# cpu_board.net
KiCad netlist of a schematic drawn in Altium Designer
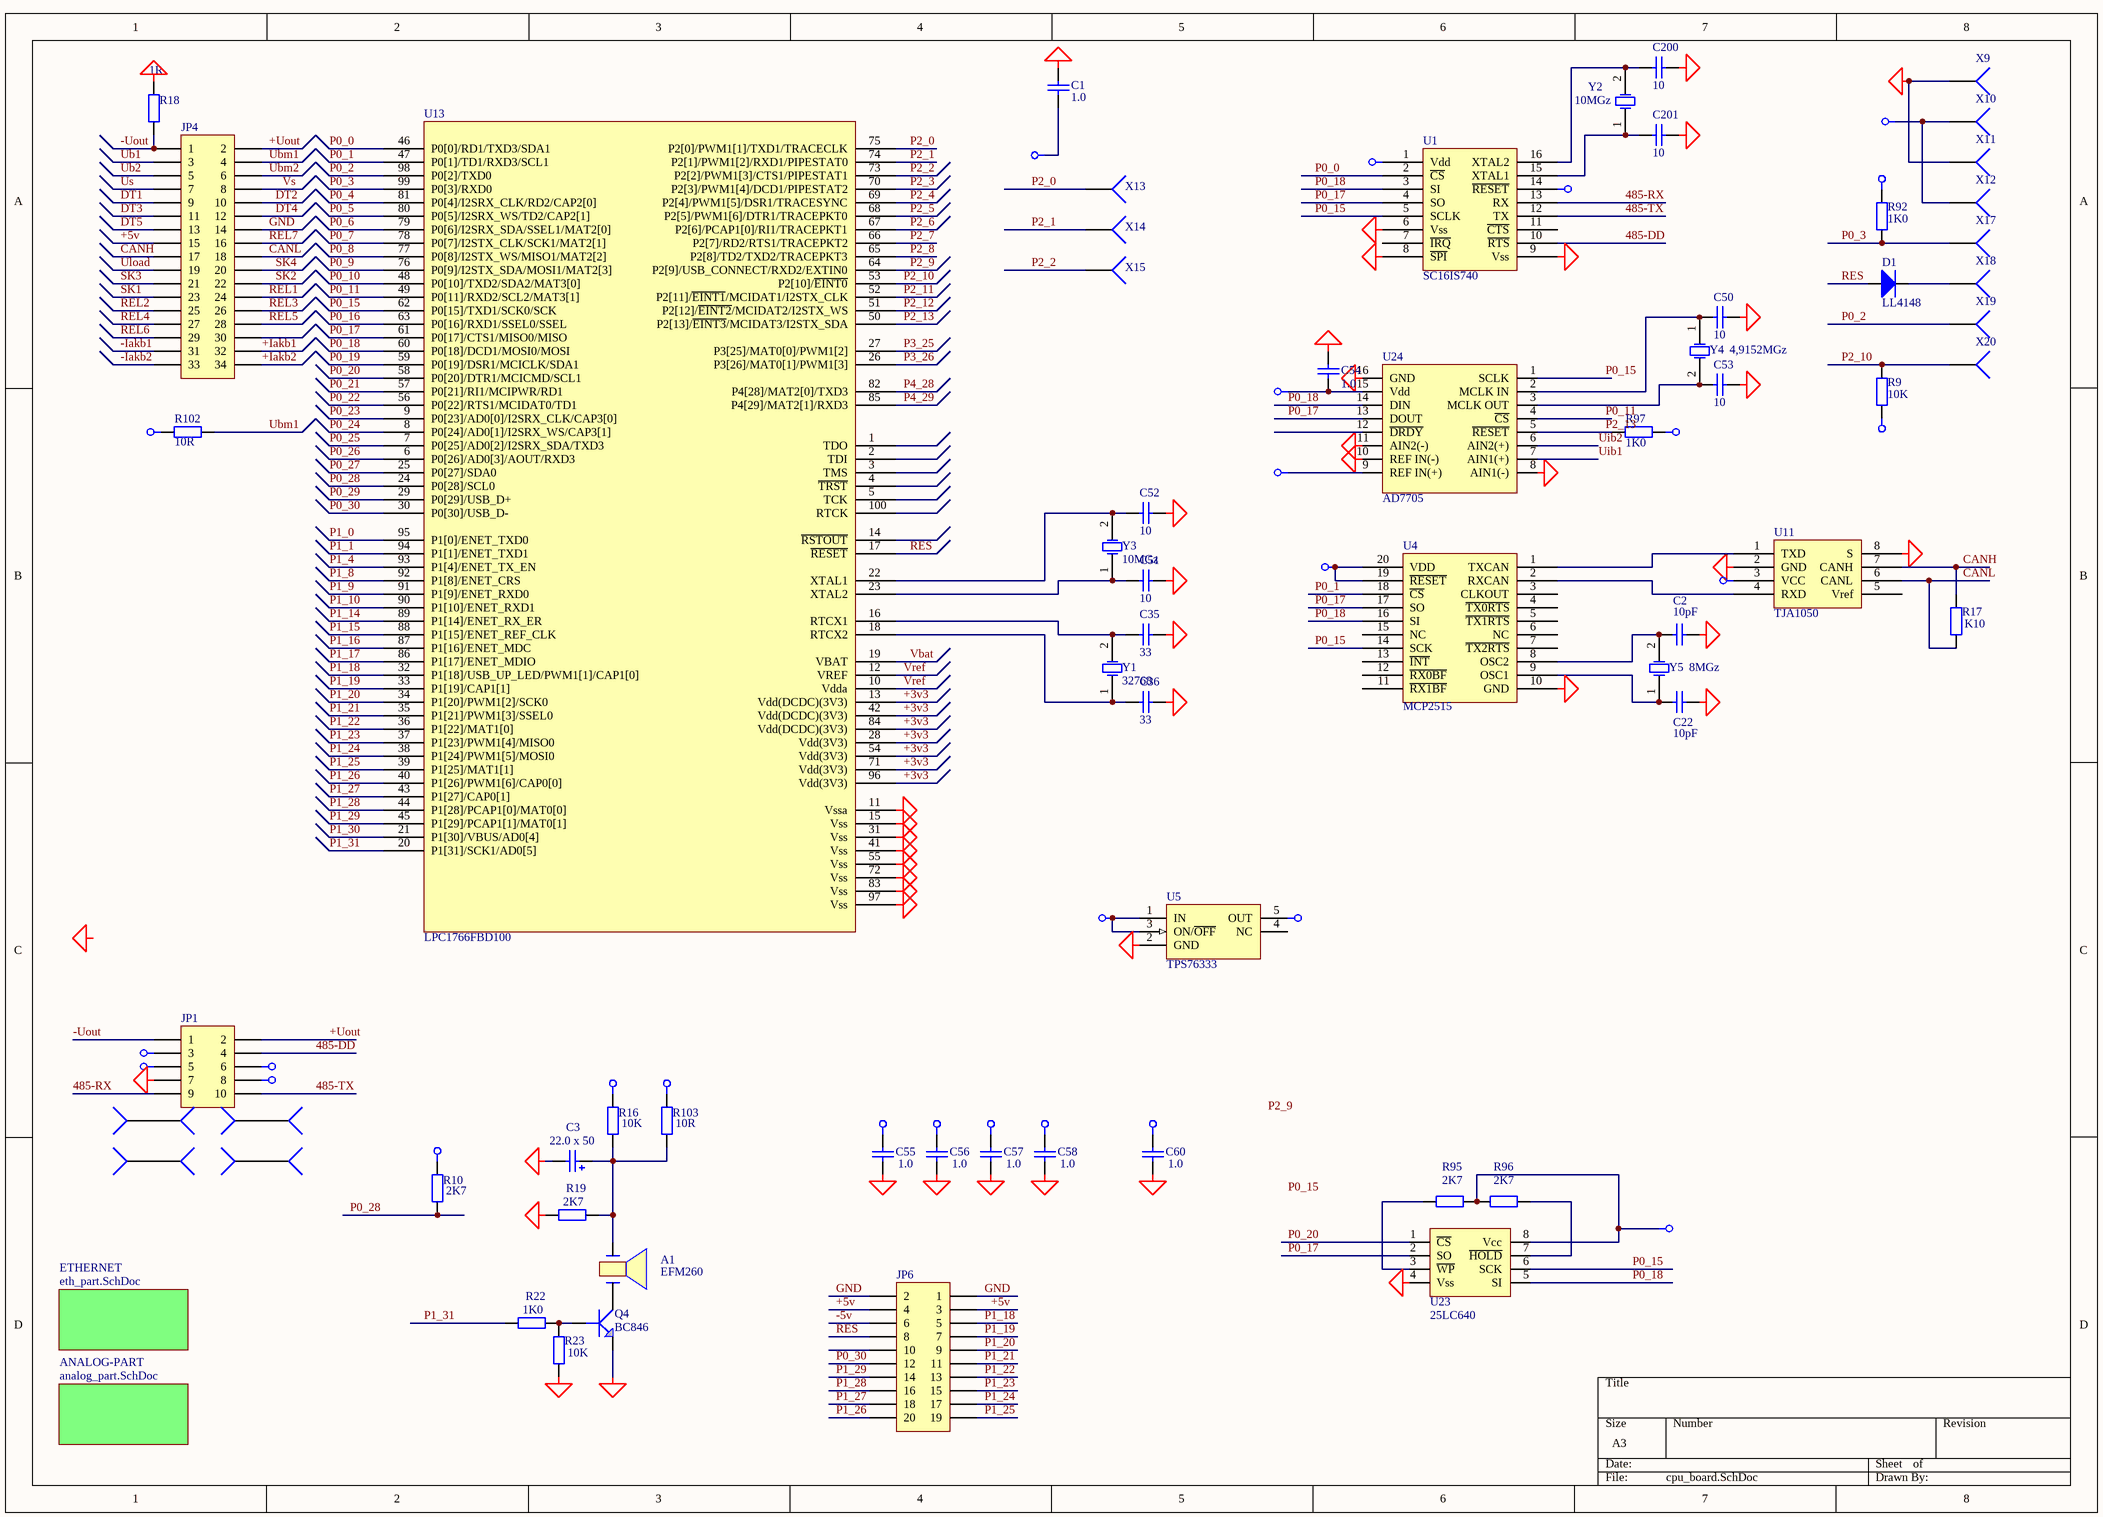
[diagram p0: cpu_board.SchDoc]

(export (version "E")
  (design (tool "Eeschema 10.0.6"))
  (components
    (comp (ref "A1")
      (value "EFM260")
      (footprint "Pjezo15")
      (description "Beeper")
      (libsource (lib "PAL") (part "PJEZ0"))
    )
    (comp (ref "C1")
      (value "1.0")
      (footprint "_1206")
      (description "Capacitor")
      (fields (field (name "MANUFACTURER") "Generic Components") (field (name "PUBLISHER") "Altium Limited"))
      (libsource (lib "Miscellaneous Devices") (part "Cap Semi"))
    )
    (comp (ref "C2")
      (value "Cap Semi")
      (footprint "_1206")
      (description "Capacitor (Semiconductor SIM Model)")
      (fields
        (field (name "MANUFACTURER") "Generic Components")
        (field (name "ALTIUM_VALUE") "10pF")
        (field (name "PUBLISHER") "Altium Limited")
      )
      (libsource (lib "Miscellaneous Devices") (part "Cap Semi"))
    )
    (comp (ref "C3")
      (value "22.0 x 50")
      (footprint "el3")
      (description "Polarized Capacitor (Radial)")
      (fields (field (name "MANUFACTURER") "Generic Components") (field (name "PUBLISHER") "Altium Limited"))
      (libsource (lib "PAL") (part "Cap Pol1"))
    )
    (comp (ref "C22")
      (value "Cap Semi")
      (footprint "_1206")
      (description "Capacitor (Semiconductor SIM Model)")
      (fields
        (field (name "MANUFACTURER") "Generic Components")
        (field (name "ALTIUM_VALUE") "10pF")
        (field (name "PUBLISHER") "Altium Limited")
      )
      (libsource (lib "Miscellaneous Devices") (part "Cap Semi"))
    )
    (comp (ref "C35")
      (value "33")
      (footprint "_1206")
      (description "Capacitor (Semiconductor SIM Model)")
      (fields (field (name "MANUFACTURER") "Generic Components") (field (name "PUBLISHER") "Altium Limited"))
      (libsource (lib "Miscellaneous Devices") (part "Cap Semi"))
    )
    (comp (ref "C36")
      (value "33")
      (footprint "_1206")
      (description "Capacitor (Semiconductor SIM Model)")
      (fields (field (name "MANUFACTURER") "Generic Components") (field (name "PUBLISHER") "Altium Limited"))
      (libsource (lib "Miscellaneous Devices") (part "Cap Semi"))
    )
    (comp (ref "C50")
      (value "10")
      (footprint "_1206")
      (description "Capacitor")
      (fields (field (name "MANUFACTURER") "Generic Components") (field (name "PUBLISHER") "Altium Limited"))
      (libsource (lib "") (part "Cap Semi_1"))
    )
    (comp (ref "C51")
      (value "10")
      (footprint "_1206")
      (description "Capacitor")
      (fields (field (name "MANUFACTURER") "Generic Components") (field (name "PUBLISHER") "Altium Limited"))
      (libsource (lib "Miscellaneous Devices") (part "Cap Semi"))
    )
    (comp (ref "C52")
      (value "10")
      (footprint "_1206")
      (description "Capacitor")
      (fields (field (name "MANUFACTURER") "Generic Components") (field (name "PUBLISHER") "Altium Limited"))
      (libsource (lib "Miscellaneous Devices") (part "Cap Semi"))
    )
    (comp (ref "C53")
      (value "10")
      (footprint "_1206")
      (description "Capacitor")
      (fields (field (name "MANUFACTURER") "Generic Components") (field (name "PUBLISHER") "Altium Limited"))
      (libsource (lib "") (part "Cap Semi_1"))
    )
    (comp (ref "C54")
      (value "1.0")
      (footprint "_1206")
      (description "Capacitor")
      (fields (field (name "MANUFACTURER") "Generic Components") (field (name "PUBLISHER") "Altium Limited"))
      (libsource (lib "Miscellaneous Devices") (part "Cap Semi"))
    )
    (comp (ref "C55")
      (value "1.0")
      (footprint "_1206")
      (description "Capacitor")
      (fields (field (name "MANUFACTURER") "Generic Components") (field (name "PUBLISHER") "Altium Limited"))
      (libsource (lib "Miscellaneous Devices") (part "Cap Semi"))
    )
    (comp (ref "C56")
      (value "1.0")
      (footprint "_1206")
      (description "Capacitor")
      (fields (field (name "MANUFACTURER") "Generic Components") (field (name "PUBLISHER") "Altium Limited"))
      (libsource (lib "Miscellaneous Devices") (part "Cap Semi"))
    )
    (comp (ref "C57")
      (value "1.0")
      (footprint "_1206")
      (description "Capacitor")
      (fields (field (name "MANUFACTURER") "Generic Components") (field (name "PUBLISHER") "Altium Limited"))
      (libsource (lib "Miscellaneous Devices") (part "Cap Semi"))
    )
    (comp (ref "C58")
      (value "1.0")
      (footprint "_1206")
      (description "Capacitor")
      (fields (field (name "MANUFACTURER") "Generic Components") (field (name "PUBLISHER") "Altium Limited"))
      (libsource (lib "Miscellaneous Devices") (part "Cap Semi"))
    )
    (comp (ref "C60")
      (value "1.0")
      (footprint "_1206")
      (description "Capacitor")
      (fields (field (name "MANUFACTURER") "Generic Components") (field (name "PUBLISHER") "Altium Limited"))
      (libsource (lib "Miscellaneous Devices") (part "Cap Semi"))
    )
    (comp (ref "C200")
      (value "10")
      (footprint "_1206")
      (description "Capacitor")
      (fields (field (name "MANUFACTURER") "Generic Components") (field (name "PUBLISHER") "Altium Limited"))
      (libsource (lib "Miscellaneous Devices") (part "Cap Semi"))
    )
    (comp (ref "C201")
      (value "10")
      (footprint "_1206")
      (description "Capacitor")
      (fields (field (name "MANUFACTURER") "Generic Components") (field (name "PUBLISHER") "Altium Limited"))
      (libsource (lib "Miscellaneous Devices") (part "Cap Semi"))
    )
    (comp (ref "D1")
      (value "LL4148")
      (footprint "_1206d")
      (description "Diode")
      (fields (field (name "MANUFACTURER") "Generic Components") (field (name "PUBLISHER") "Altium Limited"))
      (libsource (lib "PAL") (part "Diode"))
    )
    (comp (ref "JP1")
      (value "PBD-10")
      (footprint "HDR2X5")
      (description "Header, 5-Pin, Dual row")
      (fields (field (name "MANUFACTURER") "Generic Components") (field (name "PUBLISHER") "Altium Limited"))
      (libsource (lib "Miscellaneous Connectors") (part "Header 5X2"))
    )
    (comp (ref "JP4")
      (value "IDC34")
      (footprint "IDC34M")
      (description "Header, 17-Pin, Dual row")
      (fields (field (name "MANUFACTURER") "Generic Components") (field (name "PUBLISHER") "Altium Limited"))
      (libsource (lib "Miscellaneous Connectors") (part "Header 17X2"))
    )
    (comp (ref "JP6")
      (value "PBD-20")
      (footprint "HDR2X10")
      (description "Header, 10-Pin, Dual row")
      (fields (field (name "MANUFACTURER") "Generic Components") (field (name "PUBLISHER") "Altium Limited"))
      (libsource (lib "Miscellaneous Connectors") (part "Header 10X2"))
    )
    (comp (ref "Q4")
      (value "BC846")
      (footprint "SO-G3")
      (description "Bipolar transistor")
      (libsource (lib "MAIN") (part "GT122"))
    )
    (comp (ref "R9")
      (value "10K")
      (footprint "_1206")
      (description "Resistor")
      (fields (field (name "MANUFACTURER") "Generic Components") (field (name "PUBLISHER") "Altium Limited"))
      (libsource (lib "Miscellaneous Devices") (part "Res2"))
    )
    (comp (ref "R10")
      (value "2K7")
      (footprint "_1206")
      (description "Resistor")
      (fields (field (name "MANUFACTURER") "Generic Components") (field (name "PUBLISHER") "Altium Limited"))
      (libsource (lib "Miscellaneous Devices") (part "Res2"))
    )
    (comp (ref "R16")
      (value "10K")
      (footprint "_1206")
      (description "Resistor")
      (fields (field (name "MANUFACTURER") "Generic Components") (field (name "PUBLISHER") "Altium Limited"))
      (libsource (lib "Miscellaneous Devices") (part "Res2"))
    )
    (comp (ref "R17")
      (value "K10")
      (footprint "_1206")
      (description "Resistor")
      (fields (field (name "MANUFACTURER") "Generic Components") (field (name "PUBLISHER") "Altium Limited"))
      (libsource (lib "Miscellaneous Devices") (part "Res2"))
    )
    (comp (ref "R18")
      (value "1R")
      (footprint "_1206")
      (description "Resistor")
      (fields (field (name "MANUFACTURER") "Generic Components") (field (name "PUBLISHER") "Altium Limited"))
      (libsource (lib "Miscellaneous Devices") (part "Res2"))
    )
    (comp (ref "R19")
      (value "2K7")
      (footprint "_1206")
      (description "Resistor")
      (fields (field (name "MANUFACTURER") "Generic Components") (field (name "PUBLISHER") "Altium Limited"))
      (libsource (lib "") (part "Res2_1"))
    )
    (comp (ref "R22")
      (value "1K0")
      (footprint "_1206")
      (description "Resistor")
      (fields (field (name "MANUFACTURER") "Generic Components") (field (name "PUBLISHER") "Altium Limited"))
      (libsource (lib "") (part "Res2_1"))
    )
    (comp (ref "R23")
      (value "10K")
      (footprint "_1206")
      (description "Resistor")
      (fields (field (name "MANUFACTURER") "Generic Components") (field (name "PUBLISHER") "Altium Limited"))
      (libsource (lib "Miscellaneous Devices") (part "Res2"))
    )
    (comp (ref "R92")
      (value "1K0")
      (footprint "_1206")
      (description "Resistor")
      (fields (field (name "MANUFACTURER") "Generic Components") (field (name "PUBLISHER") "Altium Limited"))
      (libsource (lib "") (part "Res2_1"))
    )
    (comp (ref "R95")
      (value "2K7")
      (footprint "_1206")
      (description "Resistor")
      (fields (field (name "MANUFACTURER") "Generic Components") (field (name "PUBLISHER") "Altium Limited"))
      (libsource (lib "") (part "Res2_1"))
    )
    (comp (ref "R96")
      (value "2K7")
      (footprint "_1206")
      (description "Resistor")
      (fields (field (name "MANUFACTURER") "Generic Components") (field (name "PUBLISHER") "Altium Limited"))
      (libsource (lib "") (part "Res2_1"))
    )
    (comp (ref "R97")
      (value "1K0")
      (footprint "_1206")
      (description "Resistor")
      (fields (field (name "MANUFACTURER") "Generic Components") (field (name "PUBLISHER") "Altium Limited"))
      (libsource (lib "Miscellaneous Devices") (part "Res2"))
    )
    (comp (ref "R102")
      (value "10R")
      (footprint "_1206")
      (description "Resistor")
      (fields (field (name "MANUFACTURER") "Generic Components") (field (name "PUBLISHER") "Altium Limited"))
      (libsource (lib "") (part "Res2_2"))
    )
    (comp (ref "R103")
      (value "10R")
      (footprint "_1206")
      (description "Resistor")
      (fields (field (name "MANUFACTURER") "Generic Components") (field (name "PUBLISHER") "Altium Limited"))
      (libsource (lib "Miscellaneous Devices") (part "Res2"))
    )
    (comp (ref "U1") (value "SC16IS740") (footprint "TSSO5X6-G16") (libsource (lib "PAL") (part "SC16IS740")))
    (comp (ref "U4")
      (value "MCP2515")
      (footprint "TSSO6X6-G20/D6.6")
      (libsource (lib "PAL") (part "MCP2515"))
    )
    (comp (ref "U5")
      (value "TPS76333")
      (footprint "SO-G5/P.95")
      (description "Voltage Regulator")
      (fields
        (field (name "MANUFACTURER") "National Semiconductor")
        (field (name "PUBLISHER") "Altium Limited")
      )
      (libsource (lib "NSC Power Mgt Voltage Regulator") (part "LP2980AIM5-3.3"))
    )
    (comp (ref "U11") (value "TJA1050") (footprint "SO-G8/D5") (libsource (lib "PAL") (part "TJA1050")))
    (comp (ref "U13")
      (value "LPC1766FBD100")
      (footprint "LPC2368")
      (libsource (lib "PAL") (part "LPC2368FBD100"))
    )
    (comp (ref "U23")
      (value "25LC640")
      (footprint "SO-G8/D5")
      (description "Memory")
      (libsource (lib "PAL") (part "25LC640"))
    )
    (comp (ref "U24")
      (value "AD7705")
      (footprint "SO-G16/D10.4")
      (description "ADC")
      (libsource (lib "PAL") (part "AD7705"))
    )
    (comp (ref "X9")
      (value "~")
      (footprint "PIN1")
      (description "Socket")
      (fields (field (name "MANUFACTURER") "Generic Components") (field (name "PUBLISHER") "Altium Limited"))
      (libsource (lib "Miscellaneous Connectors") (part "Socket"))
    )
    (comp (ref "X10")
      (value "~")
      (footprint "PIN1")
      (description "Socket")
      (fields (field (name "MANUFACTURER") "Generic Components") (field (name "PUBLISHER") "Altium Limited"))
      (libsource (lib "Miscellaneous Connectors") (part "Socket"))
    )
    (comp (ref "X11")
      (value "~")
      (footprint "PIN1")
      (description "Socket")
      (fields (field (name "MANUFACTURER") "Generic Components") (field (name "PUBLISHER") "Altium Limited"))
      (libsource (lib "Miscellaneous Connectors") (part "Socket"))
    )
    (comp (ref "X12")
      (value "~")
      (footprint "PIN1")
      (description "Socket")
      (fields (field (name "MANUFACTURER") "Generic Components") (field (name "PUBLISHER") "Altium Limited"))
      (libsource (lib "Miscellaneous Connectors") (part "Socket"))
    )
    (comp (ref "X13")
      (value "~")
      (footprint "PIN1")
      (description "Socket")
      (fields (field (name "MANUFACTURER") "Generic Components") (field (name "PUBLISHER") "Altium Limited"))
      (libsource (lib "Miscellaneous Connectors") (part "Socket"))
    )
    (comp (ref "X14")
      (value "~")
      (footprint "PIN1")
      (description "Socket")
      (fields (field (name "MANUFACTURER") "Generic Components") (field (name "PUBLISHER") "Altium Limited"))
      (libsource (lib "Miscellaneous Connectors") (part "Socket"))
    )
    (comp (ref "X15")
      (value "~")
      (footprint "PIN1")
      (description "Socket")
      (fields (field (name "MANUFACTURER") "Generic Components") (field (name "PUBLISHER") "Altium Limited"))
      (libsource (lib "Miscellaneous Connectors") (part "Socket"))
    )
    (comp (ref "X16")
      (value "~")
      (footprint "PIN1")
      (description "Socket")
      (fields (field (name "MANUFACTURER") "Generic Components") (field (name "PUBLISHER") "Altium Limited"))
      (libsource (lib "Miscellaneous Connectors") (part "Socket"))
    )
    (comp (ref "X17")
      (value "~")
      (footprint "PIN1")
      (description "Socket")
      (fields (field (name "MANUFACTURER") "Generic Components") (field (name "PUBLISHER") "Altium Limited"))
      (libsource (lib "Miscellaneous Connectors") (part "Socket"))
    )
    (comp (ref "X18")
      (value "~")
      (footprint "PIN1")
      (description "Socket")
      (fields (field (name "MANUFACTURER") "Generic Components") (field (name "PUBLISHER") "Altium Limited"))
      (libsource (lib "Miscellaneous Connectors") (part "Socket"))
    )
    (comp (ref "X19")
      (value "~")
      (footprint "PIN1")
      (description "Socket")
      (fields (field (name "MANUFACTURER") "Generic Components") (field (name "PUBLISHER") "Altium Limited"))
      (libsource (lib "Miscellaneous Connectors") (part "Socket"))
    )
    (comp (ref "X20")
      (value "~")
      (footprint "PIN1")
      (description "Socket")
      (fields (field (name "MANUFACTURER") "Generic Components") (field (name "PUBLISHER") "Altium Limited"))
      (libsource (lib "Miscellaneous Connectors") (part "Socket"))
    )
    (comp (ref "X21")
      (value "~")
      (footprint "PIN1")
      (description "Socket")
      (fields (field (name "MANUFACTURER") "Generic Components") (field (name "PUBLISHER") "Altium Limited"))
      (libsource (lib "Miscellaneous Connectors") (part "Socket"))
    )
    (comp (ref "X22")
      (value "~")
      (footprint "PIN1")
      (description "Socket")
      (fields (field (name "MANUFACTURER") "Generic Components") (field (name "PUBLISHER") "Altium Limited"))
      (libsource (lib "Miscellaneous Connectors") (part "Socket"))
    )
    (comp (ref "X23")
      (value "~")
      (footprint "PIN1")
      (description "Socket")
      (fields (field (name "MANUFACTURER") "Generic Components") (field (name "PUBLISHER") "Altium Limited"))
      (libsource (lib "Miscellaneous Connectors") (part "Socket"))
    )
    (comp (ref "X24")
      (value "~")
      (footprint "PIN1")
      (description "Socket")
      (fields (field (name "MANUFACTURER") "Generic Components") (field (name "PUBLISHER") "Altium Limited"))
      (libsource (lib "Miscellaneous Connectors") (part "Socket"))
    )
    (comp (ref "X25")
      (value "~")
      (footprint "PIN1")
      (description "Socket")
      (fields (field (name "MANUFACTURER") "Generic Components") (field (name "PUBLISHER") "Altium Limited"))
      (libsource (lib "Miscellaneous Connectors") (part "Socket"))
    )
    (comp (ref "X26")
      (value "~")
      (footprint "PIN1")
      (description "Socket")
      (fields (field (name "MANUFACTURER") "Generic Components") (field (name "PUBLISHER") "Altium Limited"))
      (libsource (lib "Miscellaneous Connectors") (part "Socket"))
    )
    (comp (ref "X27")
      (value "~")
      (footprint "PIN1")
      (description "Socket")
      (fields (field (name "MANUFACTURER") "Generic Components") (field (name "PUBLISHER") "Altium Limited"))
      (libsource (lib "Miscellaneous Connectors") (part "Socket"))
    )
    (comp (ref "Y1")
      (value "32768")
      (footprint "QWARZ2")
      (description "Crystal Oscillator")
      (fields (field (name "MANUFACTURER") "Generic Components") (field (name "PUBLISHER") "Altium Limited"))
      (libsource (lib "Miscellaneous Devices") (part "XTAL"))
    )
    (comp (ref "Y2")
      (value "10MGz")
      (footprint "QWARZ1")
      (description "Crystal Oscillator")
      (fields (field (name "MANUFACTURER") "Generic Components") (field (name "PUBLISHER") "Altium Limited"))
      (libsource (lib "Miscellaneous Devices") (part "XTAL"))
    )
    (comp (ref "Y3")
      (value "10MGz")
      (footprint "QWARZ1")
      (description "Crystal Oscillator")
      (fields (field (name "MANUFACTURER") "Generic Components") (field (name "PUBLISHER") "Altium Limited"))
      (libsource (lib "Miscellaneous Devices") (part "XTAL"))
    )
    (comp (ref "Y4")
      (value "4,9152MGz")
      (footprint "QWARZ1")
      (description "Crystal Oscillator")
      (fields (field (name "MANUFACTURER") "Generic Components") (field (name "PUBLISHER") "Altium Limited"))
      (libsource (lib "") (part "XTAL_1"))
    )
    (comp (ref "Y5")
      (value "8MGz")
      (footprint "QWARZ1")
      (description "Crystal Oscillator")
      (fields (field (name "MANUFACTURER") "Generic Components") (field (name "PUBLISHER") "Altium Limited"))
      (libsource (lib "Miscellaneous Devices") (part "XTAL"))
    )
  )
  (nets
    (net (code "1") (name "+3v3") (class "Default")
      (node (ref "C1") (pin "1") (pinfunction "1_1") (pintype "passive"))
      (node (ref "C58") (pin "2") (pinfunction "2_2") (pintype "passive"))
      (node (ref "JP1") (pin "3") (pinfunction "3_3") (pintype "passive"))
      (node (ref "R10") (pin "2") (pinfunction "2_2") (pintype "passive"))
      (node (ref "R9") (pin "1") (pinfunction "1_1") (pintype "passive"))
      (node (ref "R92") (pin "2") (pinfunction "2_2") (pintype "passive"))
      (node (ref "U13") (pin "13") (pinfunction "Vdd(DCDC)(3V3)_13") (pintype "passive"))
      (node (ref "U13") (pin "28") (pinfunction "Vdd(3V3)_28") (pintype "passive"))
      (node (ref "U13") (pin "42") (pinfunction "Vdd(DCDC)(3V3)_42") (pintype "passive"))
      (node (ref "U13") (pin "54") (pinfunction "Vdd(3V3)_54") (pintype "passive"))
      (node (ref "U13") (pin "71") (pinfunction "Vdd(3V3)_71") (pintype "passive"))
      (node (ref "U13") (pin "84") (pinfunction "Vdd(DCDC)(3V3)_84") (pintype "passive"))
      (node (ref "U13") (pin "96") (pinfunction "Vdd(3V3)_96") (pintype "passive"))
    )
    (net (code "2") (name "+5v") (class "Default")
      (node (ref "C54") (pin "2") (pinfunction "2_2") (pintype "passive"))
      (node (ref "C55") (pin "2") (pinfunction "2_2") (pintype "passive"))
      (node (ref "C57") (pin "2") (pinfunction "2_2") (pintype "passive"))
      (node (ref "C60") (pin "2") (pinfunction "2_2") (pintype "passive"))
      (node (ref "JP1") (pin "5") (pinfunction "5_5") (pintype "passive"))
      (node (ref "JP4") (pin "15") (pinfunction "15_15") (pintype "passive"))
      (node (ref "JP6") (pin "3") (pinfunction "3_3") (pintype "passive"))
      (node (ref "JP6") (pin "4") (pinfunction "4_4") (pintype "passive"))
      (node (ref "R103") (pin "2") (pinfunction "2_2") (pintype "passive"))
      (node (ref "R95") (pin "2") (pinfunction "2_2") (pintype "passive"))
      (node (ref "R96") (pin "1") (pinfunction "1_1") (pintype "passive"))
      (node (ref "R97") (pin "2") (pinfunction "2_2") (pintype "passive"))
      (node (ref "U1") (pin "1") (pinfunction "Vdd_1") (pintype "passive"))
      (node (ref "U1") (pin "14") (pinfunction "~{RESET}_14") (pintype "passive"))
      (node (ref "U11") (pin "3") (pinfunction "VCC_3") (pintype "passive"))
      (node (ref "U23") (pin "8") (pinfunction "Vcc_8") (pintype "passive"))
      (node (ref "U24") (pin "15") (pinfunction "Vdd_15") (pintype "passive"))
      (node (ref "U4") (pin "19") (pinfunction "~{RESET}_19") (pintype "passive"))
      (node (ref "U4") (pin "20") (pinfunction "VDD_20") (pintype "passive"))
      (node (ref "U5") (pin "1") (pinfunction "IN_1") (pintype "power_in"))
      (node (ref "U5") (pin "3") (pinfunction "ON/~{OFF}_3") (pintype "input"))
      (node (ref "X10") (pin "1") (pinfunction "1_1") (pintype "passive"))
      (node (ref "X12") (pin "1") (pinfunction "1_1") (pintype "passive"))
    )
    (net (code "3") (name "+Uout") (class "Default")
      (node (ref "JP1") (pin "2") (pinfunction "2_2") (pintype "passive"))
      (node (ref "JP4") (pin "2") (pinfunction "2_2") (pintype "passive"))
      (node (ref "R102") (pin "2") (pinfunction "2_2") (pintype "passive"))
      (node (ref "R16") (pin "2") (pinfunction "2_2") (pintype "passive"))
    )
    (net (code "4") (name "-5v") (class "Default")
      (node (ref "C56") (pin "2") (pinfunction "2_2") (pintype "passive"))
      (node (ref "JP1") (pin "8") (pinfunction "8_8") (pintype "passive"))
      (node (ref "JP6") (pin "6") (pinfunction "6_6") (pintype "passive"))
    )
    (net (code "5") (name "/+Iakb1") (class "Default")
      (node (ref "JP4") (pin "32") (pinfunction "32_32") (pintype "passive"))
    )
    (net (code "6") (name "/+Iakb2") (class "Default")
      (node (ref "JP4") (pin "34") (pinfunction "34_34") (pintype "passive"))
    )
    (net (code "7") (name "/-Iakb1") (class "Default")
      (node (ref "JP4") (pin "31") (pinfunction "31_31") (pintype "passive"))
    )
    (net (code "8") (name "/-Iakb2") (class "Default")
      (node (ref "JP4") (pin "33") (pinfunction "33_33") (pintype "passive"))
    )
    (net (code "9") (name "/-Uout") (class "Default")
      (node (ref "JP1") (pin "1") (pinfunction "1_1") (pintype "passive"))
      (node (ref "JP4") (pin "1") (pinfunction "1_1") (pintype "passive"))
      (node (ref "R18") (pin "1") (pinfunction "1_1") (pintype "passive"))
    )
    (net (code "10") (name "/485-DD") (class "Default")
      (node (ref "JP1") (pin "4") (pinfunction "4_4") (pintype "passive"))
      (node (ref "U1") (pin "10") (pinfunction "~{RTS}_10") (pintype "passive"))
    )
    (net (code "11") (name "/485-RX") (class "Default")
      (node (ref "JP1") (pin "9") (pinfunction "9_9") (pintype "passive"))
      (node (ref "U1") (pin "13") (pinfunction "RX_13") (pintype "passive"))
    )
    (net (code "12") (name "/485-TX") (class "Default")
      (node (ref "JP1") (pin "10") (pinfunction "10_10") (pintype "passive"))
      (node (ref "U1") (pin "12") (pinfunction "TX_12") (pintype "passive"))
    )
    (net (code "13") (name "/CANH") (class "Default")
      (node (ref "JP4") (pin "17") (pinfunction "17_17") (pintype "passive"))
      (node (ref "R17") (pin "2") (pinfunction "2_2") (pintype "passive"))
      (node (ref "U11") (pin "7") (pinfunction "CANH_7") (pintype "passive"))
    )
    (net (code "14") (name "/CANL") (class "Default")
      (node (ref "JP4") (pin "18") (pinfunction "18_18") (pintype "passive"))
      (node (ref "R17") (pin "1") (pinfunction "1_1") (pintype "passive"))
      (node (ref "U11") (pin "6") (pinfunction "CANL_6") (pintype "passive"))
    )
    (net (code "15") (name "/DT1") (class "Default")
      (node (ref "JP4") (pin "9") (pinfunction "9_9") (pintype "passive"))
    )
    (net (code "16") (name "/DT2") (class "Default")
      (node (ref "JP4") (pin "10") (pinfunction "10_10") (pintype "passive"))
    )
    (net (code "17") (name "/DT3") (class "Default")
      (node (ref "JP4") (pin "11") (pinfunction "11_11") (pintype "passive"))
    )
    (net (code "18") (name "/DT4") (class "Default")
      (node (ref "JP4") (pin "12") (pinfunction "12_12") (pintype "passive"))
    )
    (net (code "19") (name "/DT5") (class "Default")
      (node (ref "JP4") (pin "13") (pinfunction "13_13") (pintype "passive"))
    )
    (net (code "20") (name "/P0_0") (class "Default")
      (node (ref "U1") (pin "2") (pinfunction "~{CS}_2") (pintype "passive"))
      (node (ref "U13") (pin "46") (pinfunction "P0[0]/RD1/TXD3/SDA1_46") (pintype "passive"))
    )
    (net (code "21") (name "/P0_1") (class "Default")
      (node (ref "U13") (pin "47") (pinfunction "P0[1]/TD1/RXD3/SCL1_47") (pintype "passive"))
      (node (ref "U4") (pin "18") (pinfunction "~{CS}_18") (pintype "passive"))
    )
    (net (code "22") (name "/P0_2") (class "Default")
      (node (ref "U13") (pin "98") (pinfunction "P0[2]/TXD0_98") (pintype "passive"))
      (node (ref "X19") (pin "1") (pinfunction "1_1") (pintype "passive"))
    )
    (net (code "23") (name "/P0_3") (class "Default")
      (node (ref "R92") (pin "1") (pinfunction "1_1") (pintype "passive"))
      (node (ref "U13") (pin "99") (pinfunction "P0[3]/RXD0_99") (pintype "passive"))
      (node (ref "X17") (pin "1") (pinfunction "1_1") (pintype "passive"))
    )
    (net (code "24") (name "/P0_4") (class "Default")
      (node (ref "U13") (pin "81") (pinfunction "P0[4]/I2SRX_CLK/RD2/CAP2[0]_81") (pintype "passive"))
    )
    (net (code "25") (name "/P0_5") (class "Default")
      (node (ref "U13") (pin "80") (pinfunction "P0[5]/I2SRX_WS/TD2/CAP2[1]_80") (pintype "passive"))
    )
    (net (code "26") (name "/P0_6") (class "Default")
      (node (ref "U13") (pin "79") (pinfunction "P0[6]/I2SRX_SDA/SSEL1/MAT2[0]_79") (pintype "passive"))
    )
    (net (code "27") (name "/P0_7") (class "Default")
      (node (ref "U13") (pin "78") (pinfunction "P0[7]/I2STX_CLK/SCK1/MAT2[1]_78") (pintype "passive"))
    )
    (net (code "28") (name "/P0_8") (class "Default")
      (node (ref "U13") (pin "77") (pinfunction "P0[8]/I2STX_WS/MISO1/MAT2[2]_77") (pintype "passive"))
    )
    (net (code "29") (name "/P0_9") (class "Default")
      (node (ref "U13") (pin "76") (pinfunction "P0[9]/I2STX_SDA/MOSI1/MAT2[3]_76") (pintype "passive"))
    )
    (net (code "30") (name "/P0_10") (class "Default")
      (node (ref "U13") (pin "48") (pinfunction "P0[10]/TXD2/SDA2/MAT3[0]_48") (pintype "passive"))
    )
    (net (code "31") (name "/P0_11") (class "Default")
      (node (ref "U13") (pin "49") (pinfunction "P0[11]/RXD2/SCL2/MAT3[1]_49") (pintype "passive"))
      (node (ref "U24") (pin "4") (pinfunction "~{CS}_4") (pintype "passive"))
    )
    (net (code "32") (name "/P0_15") (class "Default")
      (node (ref "U1") (pin "5") (pinfunction "SCLK_5") (pintype "passive"))
      (node (ref "U13") (pin "62") (pinfunction "P0[15]/TXD1/SCK0/SCK_62") (pintype "passive"))
      (node (ref "U23") (pin "6") (pinfunction "SCK_6") (pintype "passive"))
      (node (ref "U24") (pin "1") (pinfunction "SCLK_1") (pintype "passive"))
      (node (ref "U4") (pin "14") (pinfunction "SCK_14") (pintype "passive"))
    )
    (net (code "33") (name "/P0_16") (class "Default")
      (node (ref "U13") (pin "63") (pinfunction "P0[16]/RXD1/SSEL0/SSEL_63") (pintype "passive"))
    )
    (net (code "34") (name "/P0_17") (class "Default")
      (node (ref "U1") (pin "4") (pinfunction "SO_4") (pintype "passive"))
      (node (ref "U13") (pin "61") (pinfunction "P0[17]/CTS1/MISO0/MISO_61") (pintype "passive"))
      (node (ref "U23") (pin "2") (pinfunction "SO_2") (pintype "passive"))
      (node (ref "U24") (pin "13") (pinfunction "DOUT_13") (pintype "passive"))
      (node (ref "U4") (pin "17") (pinfunction "SO_17") (pintype "passive"))
    )
    (net (code "35") (name "/P0_18") (class "Default")
      (node (ref "U1") (pin "3") (pinfunction "SI_3") (pintype "passive"))
      (node (ref "U13") (pin "60") (pinfunction "P0[18]/DCD1/MOSI0/MOSI_60") (pintype "passive"))
      (node (ref "U23") (pin "5") (pinfunction "SI_5") (pintype "passive"))
      (node (ref "U24") (pin "14") (pinfunction "DIN_14") (pintype "passive"))
      (node (ref "U4") (pin "16") (pinfunction "SI_16") (pintype "passive"))
    )
    (net (code "36") (name "/P0_19") (class "Default")
      (node (ref "U13") (pin "59") (pinfunction "P0[19]/DSR1/MCICLK/SDA1_59") (pintype "passive"))
    )
    (net (code "37") (name "/P0_20") (class "Default")
      (node (ref "U13") (pin "58") (pinfunction "P0[20]/DTR1/MCICMD/SCL1_58") (pintype "passive"))
      (node (ref "U23") (pin "1") (pinfunction "~{CS}_1") (pintype "passive"))
    )
    (net (code "38") (name "/P0_21") (class "Default")
      (node (ref "U13") (pin "57") (pinfunction "P0[21]/RI1/MCIPWR/RD1_57") (pintype "passive"))
    )
    (net (code "39") (name "/P0_22") (class "Default")
      (node (ref "U13") (pin "56") (pinfunction "P0[22]/RTS1/MCIDAT0/TD1_56") (pintype "passive"))
    )
    (net (code "40") (name "/P0_23") (class "Default")
      (node (ref "U13") (pin "9") (pinfunction "P0[23]/AD0[0]/I2SRX_CLK/CAP3[0]_9") (pintype "passive"))
    )
    (net (code "41") (name "/P0_24") (class "Default")
      (node (ref "U13") (pin "8") (pinfunction "P0[24]/AD0[1]/I2SRX_WS/CAP3[1]_8") (pintype "passive"))
    )
    (net (code "42") (name "/P0_25") (class "Default")
      (node (ref "U13") (pin "7") (pinfunction "P0[25]/AD0[2]/I2SRX_SDA/TXD3_7") (pintype "passive"))
    )
    (net (code "43") (name "/P0_26") (class "Default")
      (node (ref "U13") (pin "6") (pinfunction "P0[26]/AD0[3]/AOUT/RXD3_6") (pintype "passive"))
    )
    (net (code "44") (name "/P0_27") (class "Default")
      (node (ref "U13") (pin "25") (pinfunction "P0[27]/SDA0_25") (pintype "passive"))
    )
    (net (code "45") (name "/P0_28") (class "Default")
      (node (ref "R10") (pin "1") (pinfunction "1_1") (pintype "passive"))
      (node (ref "U13") (pin "24") (pinfunction "P0[28]/SCL0_24") (pintype "passive"))
    )
    (net (code "46") (name "/P0_29") (class "Default")
      (node (ref "U13") (pin "29") (pinfunction "P0[29]/USB_D+_29") (pintype "passive"))
    )
    (net (code "47") (name "/P0_30") (class "Default")
      (node (ref "JP6") (pin "12") (pinfunction "12_12") (pintype "passive"))
      (node (ref "U13") (pin "30") (pinfunction "P0[30]/USB_D-_30") (pintype "passive"))
    )
    (net (code "48") (name "/P1_0") (class "Default")
      (node (ref "U13") (pin "95") (pinfunction "P1[0]/ENET_TXD0_95") (pintype "passive"))
    )
    (net (code "49") (name "/P1_1") (class "Default")
      (node (ref "U13") (pin "94") (pinfunction "P1[1]/ENET_TXD1_94") (pintype "passive"))
    )
    (net (code "50") (name "/P1_4") (class "Default")
      (node (ref "U13") (pin "93") (pinfunction "P1[4]/ENET_TX_EN_93") (pintype "passive"))
    )
    (net (code "51") (name "/P1_8") (class "Default")
      (node (ref "U13") (pin "92") (pinfunction "P1[8]/ENET_CRS_92") (pintype "passive"))
    )
    (net (code "52") (name "/P1_9") (class "Default")
      (node (ref "U13") (pin "91") (pinfunction "P1[9]/ENET_RXD0_91") (pintype "passive"))
    )
    (net (code "53") (name "/P1_10") (class "Default")
      (node (ref "U13") (pin "90") (pinfunction "P1[10]/ENET_RXD1_90") (pintype "passive"))
    )
    (net (code "54") (name "/P1_14") (class "Default")
      (node (ref "U13") (pin "89") (pinfunction "P1[14]/ENET_RX_ER_89") (pintype "passive"))
    )
    (net (code "55") (name "/P1_15") (class "Default")
      (node (ref "U13") (pin "88") (pinfunction "P1[15]/ENET_REF_CLK_88") (pintype "passive"))
    )
    (net (code "56") (name "/P1_16") (class "Default")
      (node (ref "U13") (pin "87") (pinfunction "P1[16]/ENET_MDC_87") (pintype "passive"))
    )
    (net (code "57") (name "/P1_17") (class "Default")
      (node (ref "U13") (pin "86") (pinfunction "P1[17]/ENET_MDIO_86") (pintype "passive"))
    )
    (net (code "58") (name "/P1_18") (class "Default")
      (node (ref "JP6") (pin "5") (pinfunction "5_5") (pintype "passive"))
      (node (ref "U13") (pin "32") (pinfunction "P1[18]/USB_UP_LED/PWM1[1]/CAP1[0]_32") (pintype "passive"))
    )
    (net (code "59") (name "/P1_19") (class "Default")
      (node (ref "JP6") (pin "7") (pinfunction "7_7") (pintype "passive"))
      (node (ref "U13") (pin "33") (pinfunction "P1[19]/CAP1[1]_33") (pintype "passive"))
    )
    (net (code "60") (name "/P1_20") (class "Default")
      (node (ref "JP6") (pin "9") (pinfunction "9_9") (pintype "passive"))
      (node (ref "U13") (pin "34") (pinfunction "P1[20]/PWM1[2]/SCK0_34") (pintype "passive"))
    )
    (net (code "61") (name "/P1_21") (class "Default")
      (node (ref "JP6") (pin "11") (pinfunction "11_11") (pintype "passive"))
      (node (ref "U13") (pin "35") (pinfunction "P1[21]/PWM1[3]/SSEL0_35") (pintype "passive"))
    )
    (net (code "62") (name "/P1_22") (class "Default")
      (node (ref "JP6") (pin "13") (pinfunction "13_13") (pintype "passive"))
      (node (ref "U13") (pin "36") (pinfunction "P1[22]/MAT1[0]_36") (pintype "passive"))
    )
    (net (code "63") (name "/P1_23") (class "Default")
      (node (ref "JP6") (pin "15") (pinfunction "15_15") (pintype "passive"))
      (node (ref "U13") (pin "37") (pinfunction "P1[23]/PWM1[4]/MISO0_37") (pintype "passive"))
    )
    (net (code "64") (name "/P1_24") (class "Default")
      (node (ref "JP6") (pin "17") (pinfunction "17_17") (pintype "passive"))
      (node (ref "U13") (pin "38") (pinfunction "P1[24]/PWM1[5]/MOSI0_38") (pintype "passive"))
    )
    (net (code "65") (name "/P1_25") (class "Default")
      (node (ref "JP6") (pin "19") (pinfunction "19_19") (pintype "passive"))
      (node (ref "U13") (pin "39") (pinfunction "P1[25]/MAT1[1]_39") (pintype "passive"))
    )
    (net (code "66") (name "/P1_26") (class "Default")
      (node (ref "JP6") (pin "20") (pinfunction "20_20") (pintype "passive"))
      (node (ref "U13") (pin "40") (pinfunction "P1[26]/PWM1[6]/CAP0[0]_40") (pintype "passive"))
    )
    (net (code "67") (name "/P1_27") (class "Default")
      (node (ref "JP6") (pin "18") (pinfunction "18_18") (pintype "passive"))
      (node (ref "U13") (pin "43") (pinfunction "P1[27]/CAP0[1]_43") (pintype "passive"))
    )
    (net (code "68") (name "/P1_28") (class "Default")
      (node (ref "JP6") (pin "16") (pinfunction "16_16") (pintype "passive"))
      (node (ref "U13") (pin "44") (pinfunction "P1[28]/PCAP1[0]/MAT0[0]_44") (pintype "passive"))
    )
    (net (code "69") (name "/P1_29") (class "Default")
      (node (ref "JP6") (pin "14") (pinfunction "14_14") (pintype "passive"))
      (node (ref "U13") (pin "45") (pinfunction "P1[29]/PCAP1[1]/MAT0[1]_45") (pintype "passive"))
    )
    (net (code "70") (name "/P1_30") (class "Default")
      (node (ref "U13") (pin "21") (pinfunction "P1[30]/VBUS/AD0[4]_21") (pintype "passive"))
    )
    (net (code "71") (name "/P1_31") (class "Default")
      (node (ref "R22") (pin "1") (pinfunction "1_1") (pintype "passive"))
      (node (ref "U13") (pin "20") (pinfunction "P1[31]/SCK1/AD0[5]_20") (pintype "passive"))
    )
    (net (code "72") (name "/P2_0") (class "Default")
      (node (ref "U13") (pin "75") (pinfunction "P2[0]/PWM1[1]/TXD1/TRACECLK_75") (pintype "passive"))
      (node (ref "X13") (pin "1") (pinfunction "1_1") (pintype "passive"))
    )
    (net (code "73") (name "/P2_1") (class "Default")
      (node (ref "U13") (pin "74") (pinfunction "P2[1]/PWM1[2]/RXD1/PIPESTAT0_74") (pintype "passive"))
      (node (ref "X14") (pin "1") (pinfunction "1_1") (pintype "passive"))
    )
    (net (code "74") (name "/P2_2") (class "Default")
      (node (ref "U13") (pin "73") (pinfunction "P2[2]/PWM1[3]/CTS1/PIPESTAT1_73") (pintype "passive"))
      (node (ref "X15") (pin "1") (pinfunction "1_1") (pintype "passive"))
    )
    (net (code "75") (name "/P2_3") (class "Default")
      (node (ref "U13") (pin "70") (pinfunction "P2[3]/PWM1[4]/DCD1/PIPESTAT2_70") (pintype "passive"))
    )
    (net (code "76") (name "/P2_4") (class "Default")
      (node (ref "U13") (pin "69") (pinfunction "P2[4]/PWM1[5]/DSR1/TRACESYNC_69") (pintype "passive"))
    )
    (net (code "77") (name "/P2_5") (class "Default")
      (node (ref "U13") (pin "68") (pinfunction "P2[5]/PWM1[6]/DTR1/TRACEPKT0_68") (pintype "passive"))
    )
    (net (code "78") (name "/P2_6") (class "Default")
      (node (ref "U13") (pin "67") (pinfunction "P2[6]/PCAP1[0]/RI1/TRACEPKT1_67") (pintype "passive"))
    )
    (net (code "79") (name "/P2_7") (class "Default")
      (node (ref "U13") (pin "66") (pinfunction "P2[7]/RD2/RTS1/TRACEPKT2_66") (pintype "passive"))
    )
    (net (code "80") (name "/P2_8") (class "Default")
      (node (ref "U13") (pin "65") (pinfunction "P2[8]/TD2/TXD2/TRACEPKT3_65") (pintype "passive"))
    )
    (net (code "81") (name "/P2_9") (class "Default")
      (node (ref "U13") (pin "64") (pinfunction "P2[9]/USB_CONNECT/RXD2/EXTIN0_64") (pintype "passive"))
    )
    (net (code "82") (name "/P2_10") (class "Default")
      (node (ref "R9") (pin "2") (pinfunction "2_2") (pintype "passive"))
      (node (ref "U13") (pin "53") (pinfunction "P2[10]/~{EINT0}_53") (pintype "passive"))
      (node (ref "X20") (pin "1") (pinfunction "1_1") (pintype "passive"))
    )
    (net (code "83") (name "/P2_11") (class "Default")
      (node (ref "U13") (pin "52") (pinfunction "P2[11]/~{EINT1}/MCIDAT1/I2STX_CLK_52") (pintype "passive"))
    )
    (net (code "84") (name "/P2_12") (class "Default")
      (node (ref "U13") (pin "51") (pinfunction "P2[12]/~{EINT2}/MCIDAT2/I2STX_WS_51") (pintype "passive"))
    )
    (net (code "85") (name "/P2_13") (class "Default")
      (node (ref "R97") (pin "1") (pinfunction "1_1") (pintype "passive"))
      (node (ref "U13") (pin "50") (pinfunction "P2[13]/~{EINT3}/MCIDAT3/I2STX_SDA_50") (pintype "passive"))
      (node (ref "U24") (pin "5") (pinfunction "~{RESET}_5") (pintype "passive"))
    )
    (net (code "86") (name "/P3_25") (class "Default")
      (node (ref "U13") (pin "27") (pinfunction "P3[25]/MAT0[0]/PWM1[2]_27") (pintype "passive"))
    )
    (net (code "87") (name "/P3_26") (class "Default")
      (node (ref "U13") (pin "26") (pinfunction "P3[26]/MAT0[1]/PWM1[3]_26") (pintype "passive"))
    )
    (net (code "88") (name "/P4_28") (class "Default")
      (node (ref "U13") (pin "82") (pinfunction "P4[28]/MAT2[0]/TXD3_82") (pintype "passive"))
    )
    (net (code "89") (name "/P4_29") (class "Default")
      (node (ref "U13") (pin "85") (pinfunction "P4[29]/MAT2[1]/RXD3_85") (pintype "passive"))
    )
    (net (code "90") (name "/REL1") (class "Default")
      (node (ref "JP4") (pin "24") (pinfunction "24_24") (pintype "passive"))
    )
    (net (code "91") (name "/REL2") (class "Default")
      (node (ref "JP4") (pin "25") (pinfunction "25_25") (pintype "passive"))
    )
    (net (code "92") (name "/REL3") (class "Default")
      (node (ref "JP4") (pin "26") (pinfunction "26_26") (pintype "passive"))
    )
    (net (code "93") (name "/REL4") (class "Default")
      (node (ref "JP4") (pin "27") (pinfunction "27_27") (pintype "passive"))
    )
    (net (code "94") (name "/REL5") (class "Default")
      (node (ref "JP4") (pin "28") (pinfunction "28_28") (pintype "passive"))
    )
    (net (code "95") (name "/REL6") (class "Default")
      (node (ref "JP4") (pin "29") (pinfunction "29_29") (pintype "passive"))
    )
    (net (code "96") (name "/REL7") (class "Default")
      (node (ref "JP4") (pin "16") (pinfunction "16_16") (pintype "passive"))
    )
    (net (code "97") (name "/RES") (class "Default")
      (node (ref "D1") (pin "1") (pinfunction "A_1") (pintype "passive"))
      (node (ref "JP6") (pin "8") (pinfunction "8_8") (pintype "passive"))
      (node (ref "U13") (pin "17") (pinfunction "~{RESET}_17") (pintype "passive"))
    )
    (net (code "98") (name "/SK1") (class "Default")
      (node (ref "JP4") (pin "23") (pinfunction "23_23") (pintype "passive"))
    )
    (net (code "99") (name "/SK2") (class "Default")
      (node (ref "JP4") (pin "22") (pinfunction "22_22") (pintype "passive"))
    )
    (net (code "100") (name "/SK3") (class "Default")
      (node (ref "JP4") (pin "21") (pinfunction "21_21") (pintype "passive"))
    )
    (net (code "101") (name "/SK4") (class "Default")
      (node (ref "JP4") (pin "20") (pinfunction "20_20") (pintype "passive"))
    )
    (net (code "102") (name "/Ub1") (class "Default")
      (node (ref "JP4") (pin "3") (pinfunction "3_3") (pintype "passive"))
    )
    (net (code "103") (name "/Ub2") (class "Default")
      (node (ref "JP4") (pin "5") (pinfunction "5_5") (pintype "passive"))
    )
    (net (code "104") (name "/Ubm1") (class "Default")
      (node (ref "JP4") (pin "4") (pinfunction "4_4") (pintype "passive"))
      (node (ref "R102") (pin "1") (pinfunction "1_1") (pintype "passive"))
    )
    (net (code "105") (name "/Ubm2") (class "Default")
      (node (ref "JP4") (pin "6") (pinfunction "6_6") (pintype "passive"))
    )
    (net (code "106") (name "/Uib1") (class "Default")
      (node (ref "U24") (pin "7") (pinfunction "AIN1(+)_7") (pintype "passive"))
    )
    (net (code "107") (name "/Uib2") (class "Default")
      (node (ref "U24") (pin "6") (pinfunction "AIN2(+)_6") (pintype "passive"))
    )
    (net (code "108") (name "/Uload") (class "Default")
      (node (ref "JP4") (pin "19") (pinfunction "19_19") (pintype "passive"))
    )
    (net (code "109") (name "/Us") (class "Default")
      (node (ref "JP4") (pin "7") (pinfunction "7_7") (pintype "passive"))
    )
    (net (code "110") (name "/Vs") (class "Default")
      (node (ref "JP4") (pin "8") (pinfunction "8_8") (pintype "passive"))
    )
    (net (code "111") (name "GND") (class "Default")
      (node (ref "C1") (pin "2") (pinfunction "2_2") (pintype "passive"))
      (node (ref "C2") (pin "1") (pinfunction "1_1") (pintype "passive"))
      (node (ref "C200") (pin "1") (pinfunction "1_1") (pintype "passive"))
      (node (ref "C201") (pin "1") (pinfunction "1_1") (pintype "passive"))
      (node (ref "C22") (pin "1") (pinfunction "1_1") (pintype "passive"))
      (node (ref "C3") (pin "2") (pinfunction "2_2") (pintype "passive"))
      (node (ref "C35") (pin "1") (pinfunction "1_1") (pintype "passive"))
      (node (ref "C36") (pin "1") (pinfunction "1_1") (pintype "passive"))
      (node (ref "C50") (pin "1") (pinfunction "1_1") (pintype "passive"))
      (node (ref "C51") (pin "1") (pinfunction "1_1") (pintype "passive"))
      (node (ref "C52") (pin "1") (pinfunction "1_1") (pintype "passive"))
      (node (ref "C53") (pin "1") (pinfunction "1_1") (pintype "passive"))
      (node (ref "C54") (pin "1") (pinfunction "1_1") (pintype "passive"))
      (node (ref "C55") (pin "1") (pinfunction "1_1") (pintype "passive"))
      (node (ref "C56") (pin "1") (pinfunction "1_1") (pintype "passive"))
      (node (ref "C57") (pin "1") (pinfunction "1_1") (pintype "passive"))
      (node (ref "C58") (pin "1") (pinfunction "1_1") (pintype "passive"))
      (node (ref "C60") (pin "1") (pinfunction "1_1") (pintype "passive"))
      (node (ref "JP1") (pin "7") (pinfunction "7_7") (pintype "passive"))
      (node (ref "JP4") (pin "14") (pinfunction "14_14") (pintype "passive"))
      (node (ref "JP6") (pin "1") (pinfunction "1_1") (pintype "passive"))
      (node (ref "JP6") (pin "2") (pinfunction "2_2") (pintype "passive"))
      (node (ref "Q4") (pin "2") (pinfunction "E_2") (pintype "passive"))
      (node (ref "R18") (pin "2") (pinfunction "2_2") (pintype "passive"))
      (node (ref "R19") (pin "1") (pinfunction "1_1") (pintype "passive"))
      (node (ref "R23") (pin "1") (pinfunction "1_1") (pintype "passive"))
      (node (ref "U1") (pin "6") (pinfunction "Vss_6") (pintype "passive"))
      (node (ref "U1") (pin "8") (pinfunction "~{SPI}_8") (pintype "passive"))
      (node (ref "U1") (pin "9") (pinfunction "Vss_9") (pintype "passive"))
      (node (ref "U11") (pin "2") (pinfunction "GND_2") (pintype "passive"))
      (node (ref "U11") (pin "8") (pinfunction "S_8") (pintype "passive"))
      (node (ref "U13") (pin "11") (pinfunction "Vssa_11") (pintype "passive"))
      (node (ref "U13") (pin "15") (pinfunction "Vss_15") (pintype "passive"))
      (node (ref "U13") (pin "31") (pinfunction "Vss_31") (pintype "passive"))
      (node (ref "U13") (pin "41") (pinfunction "Vss_41") (pintype "passive"))
      (node (ref "U13") (pin "55") (pinfunction "Vss_55") (pintype "passive"))
      (node (ref "U13") (pin "72") (pinfunction "Vss_72") (pintype "passive"))
      (node (ref "U13") (pin "83") (pinfunction "Vss_83") (pintype "passive"))
      (node (ref "U13") (pin "97") (pinfunction "Vss_97") (pintype "passive"))
      (node (ref "U23") (pin "4") (pinfunction "Vss_4") (pintype "passive"))
      (node (ref "U24") (pin "10") (pinfunction "REF_IN(-)_10") (pintype "passive"))
      (node (ref "U24") (pin "11") (pinfunction "AIN2(-)_11") (pintype "passive"))
      (node (ref "U24") (pin "16") (pinfunction "GND_16") (pintype "passive"))
      (node (ref "U24") (pin "8") (pinfunction "AIN1(-)_8") (pintype "passive"))
      (node (ref "U4") (pin "10") (pinfunction "GND_10") (pintype "passive"))
      (node (ref "U5") (pin "2") (pinfunction "GND_2") (pintype "power_in"))
      (node (ref "X11") (pin "1") (pinfunction "1_1") (pintype "passive"))
      (node (ref "X9") (pin "1") (pinfunction "1_1") (pintype "passive"))
    )
    (net (code "112") (name "Net-(A1-Pad2)") (class "Default")
      (node (ref "A1") (pin "2") (pinfunction "2_2") (pintype "passive"))
      (node (ref "C3") (pin "1") (pinfunction "1_1") (pintype "passive"))
      (node (ref "R103") (pin "1") (pinfunction "1_1") (pintype "passive"))
      (node (ref "R16") (pin "1") (pinfunction "1_1") (pintype "passive"))
      (node (ref "R19") (pin "2") (pinfunction "2_2") (pintype "passive"))
    )
    (net (code "113") (name "Net-(D1-K)") (class "Default")
      (node (ref "D1") (pin "2") (pinfunction "K_2") (pintype "passive"))
      (node (ref "X18") (pin "1") (pinfunction "1_1") (pintype "passive"))
    )
    (net (code "114") (name "Net-(Q4-B)") (class "Default")
      (node (ref "Q4") (pin "1") (pinfunction "B_1") (pintype "passive"))
      (node (ref "R22") (pin "2") (pinfunction "2_2") (pintype "passive"))
      (node (ref "R23") (pin "2") (pinfunction "2_2") (pintype "passive"))
    )
    (net (code "115") (name "Net-(Q4-C)") (class "Default")
      (node (ref "A1") (pin "1") (pinfunction "1_1") (pintype "passive"))
      (node (ref "Q4") (pin "3") (pinfunction "C_3") (pintype "passive"))
    )
    (net (code "116") (name "Net-(U1-XTAL1)") (class "Default")
      (node (ref "C201") (pin "2") (pinfunction "2_2") (pintype "passive"))
      (node (ref "U1") (pin "15") (pinfunction "XTAL1_15") (pintype "passive"))
      (node (ref "Y2") (pin "1") (pinfunction "OSC1_1") (pintype "passive"))
    )
    (net (code "117") (name "Net-(U1-XTAL2)") (class "Default")
      (node (ref "C200") (pin "2") (pinfunction "2_2") (pintype "passive"))
      (node (ref "U1") (pin "16") (pinfunction "XTAL2_16") (pintype "passive"))
      (node (ref "Y2") (pin "2") (pinfunction "OSC2_2") (pintype "passive"))
    )
    (net (code "118") (name "Net-(U4-OSC1)") (class "Default")
      (node (ref "C22") (pin "2") (pinfunction "2_2") (pintype "passive"))
      (node (ref "U4") (pin "9") (pinfunction "OSC1_9") (pintype "passive"))
      (node (ref "Y5") (pin "1") (pinfunction "OSC1_1") (pintype "passive"))
    )
    (net (code "119") (name "Net-(U4-OSC2)") (class "Default")
      (node (ref "C2") (pin "2") (pinfunction "2_2") (pintype "passive"))
      (node (ref "U4") (pin "8") (pinfunction "OSC2_8") (pintype "passive"))
      (node (ref "Y5") (pin "2") (pinfunction "OSC2_2") (pintype "passive"))
    )
    (net (code "120") (name "Net-(U11-RXD)") (class "Default")
      (node (ref "U11") (pin "4") (pinfunction "RXD_4") (pintype "passive"))
      (node (ref "U4") (pin "2") (pinfunction "RXCAN_2") (pintype "passive"))
    )
    (net (code "121") (name "Net-(U11-TXD)") (class "Default")
      (node (ref "U11") (pin "1") (pinfunction "TXD_1") (pintype "passive"))
      (node (ref "U4") (pin "1") (pinfunction "TXCAN_1") (pintype "passive"))
    )
    (net (code "122") (name "Net-(U13-RTCX1)") (class "Default")
      (node (ref "C35") (pin "2") (pinfunction "2_2") (pintype "passive"))
      (node (ref "U13") (pin "16") (pinfunction "RTCX1_16") (pintype "passive"))
      (node (ref "Y1") (pin "2") (pinfunction "OSC2_2") (pintype "passive"))
    )
    (net (code "123") (name "Net-(U13-RTCX2)") (class "Default")
      (node (ref "C36") (pin "2") (pinfunction "2_2") (pintype "passive"))
      (node (ref "U13") (pin "18") (pinfunction "RTCX2_18") (pintype "passive"))
      (node (ref "Y1") (pin "1") (pinfunction "OSC1_1") (pintype "passive"))
    )
    (net (code "124") (name "Net-(U13-XTAL1)") (class "Default")
      (node (ref "C52") (pin "2") (pinfunction "2_2") (pintype "passive"))
      (node (ref "U13") (pin "22") (pinfunction "XTAL1_22") (pintype "passive"))
      (node (ref "Y3") (pin "2") (pinfunction "OSC2_2") (pintype "passive"))
    )
    (net (code "125") (name "Net-(U13-XTAL2)") (class "Default")
      (node (ref "C51") (pin "2") (pinfunction "2_2") (pintype "passive"))
      (node (ref "U13") (pin "23") (pinfunction "XTAL2_23") (pintype "passive"))
      (node (ref "Y3") (pin "1") (pinfunction "OSC1_1") (pintype "passive"))
    )
    (net (code "126") (name "Net-(U23-~{HOLD})") (class "Default")
      (node (ref "R96") (pin "2") (pinfunction "2_2") (pintype "passive"))
      (node (ref "U23") (pin "7") (pinfunction "~{HOLD}_7") (pintype "passive"))
    )
    (net (code "127") (name "Net-(U23-~{WP})") (class "Default")
      (node (ref "R95") (pin "1") (pinfunction "1_1") (pintype "passive"))
      (node (ref "U23") (pin "3") (pinfunction "~{WP}_3") (pintype "passive"))
    )
    (net (code "128") (name "Net-(U24-MCLK_IN)") (class "Default")
      (node (ref "C50") (pin "2") (pinfunction "2_2") (pintype "passive"))
      (node (ref "U24") (pin "2") (pinfunction "MCLK_IN_2") (pintype "passive"))
      (node (ref "Y4") (pin "1") (pinfunction "OSC1_1") (pintype "passive"))
    )
    (net (code "129") (name "Net-(U24-MCLK_OUT)") (class "Default")
      (node (ref "C53") (pin "2") (pinfunction "2_2") (pintype "passive"))
      (node (ref "U24") (pin "3") (pinfunction "MCLK_OUT_3") (pintype "passive"))
      (node (ref "Y4") (pin "2") (pinfunction "OSC2_2") (pintype "passive"))
    )
    (net (code "130") (name "Net-(X16-Pad1)") (class "Default")
      (node (ref "X16") (pin "1") (pinfunction "1_1") (pintype "passive"))
      (node (ref "X22") (pin "1") (pinfunction "1_1") (pintype "passive"))
    )
    (net (code "131") (name "Net-(X21-Pad1)") (class "Default")
      (node (ref "X21") (pin "1") (pinfunction "1_1") (pintype "passive"))
      (node (ref "X23") (pin "1") (pinfunction "1_1") (pintype "passive"))
    )
    (net (code "132") (name "Net-(X24-Pad1)") (class "Default")
      (node (ref "X24") (pin "1") (pinfunction "1_1") (pintype "passive"))
      (node (ref "X26") (pin "1") (pinfunction "1_1") (pintype "passive"))
    )
    (net (code "133") (name "Net-(X25-Pad1)") (class "Default")
      (node (ref "X25") (pin "1") (pinfunction "1_1") (pintype "passive"))
      (node (ref "X27") (pin "1") (pinfunction "1_1") (pintype "passive"))
    )
    (net (code "134") (name "Vbat") (class "Default")
      (node (ref "JP1") (pin "6") (pinfunction "6_6") (pintype "passive"))
      (node (ref "U13") (pin "19") (pinfunction "VBAT_19") (pintype "passive"))
    )
    (net (code "135") (name "Vref") (class "Default")
      (node (ref "U13") (pin "10") (pinfunction "Vdda_10") (pintype "passive"))
      (node (ref "U13") (pin "12") (pinfunction "VREF_12") (pintype "passive"))
      (node (ref "U24") (pin "9") (pinfunction "REF_IN(+)_9") (pintype "passive"))
      (node (ref "U5") (pin "5") (pinfunction "OUT_5") (pintype "power_in"))
    )
    (net (code "136") (name "unconnected-(JP4-Pad30)") (class "Default")
      (node (ref "JP4") (pin "30") (pinfunction "30_30") (pintype "passive"))
    )
    (net (code "137") (name "unconnected-(JP6-Pad10)") (class "Default")
      (node (ref "JP6") (pin "10") (pinfunction "10_10") (pintype "passive"))
    )
    (net (code "138") (name "unconnected-(U1-~{CTS}-Pad11)") (class "Default")
      (node (ref "U1") (pin "11") (pinfunction "~{CTS}_11") (pintype "passive"))
    )
    (net (code "139") (name "unconnected-(U1-~{IRQ}-Pad7)") (class "Default")
      (node (ref "U1") (pin "7") (pinfunction "~{IRQ}_7") (pintype "passive"))
    )
    (net (code "140") (name "unconnected-(U4-CLKOUT-Pad3)") (class "Default")
      (node (ref "U4") (pin "3") (pinfunction "CLKOUT_3") (pintype "passive"))
    )
    (net (code "141") (name "unconnected-(U4-NC-Pad6)") (class "Default")
      (node (ref "U4") (pin "6") (pinfunction "NC_6") (pintype "passive"))
    )
    (net (code "142") (name "unconnected-(U4-NC-Pad15)") (class "Default")
      (node (ref "U4") (pin "15") (pinfunction "NC_15") (pintype "passive"))
    )
    (net (code "143") (name "unconnected-(U4-~{INT}-Pad13)") (class "Default")
      (node (ref "U4") (pin "13") (pinfunction "~{INT}_13") (pintype "passive"))
    )
    (net (code "144") (name "unconnected-(U4-~{RX0BF}-Pad12)") (class "Default")
      (node (ref "U4") (pin "12") (pinfunction "~{RX0BF}_12") (pintype "passive"))
    )
    (net (code "145") (name "unconnected-(U4-~{RX1BF}-Pad11)") (class "Default")
      (node (ref "U4") (pin "11") (pinfunction "~{RX1BF}_11") (pintype "passive"))
    )
    (net (code "146") (name "unconnected-(U4-~{TX0RTS}-Pad4)") (class "Default")
      (node (ref "U4") (pin "4") (pinfunction "~{TX0RTS}_4") (pintype "passive"))
    )
    (net (code "147") (name "unconnected-(U4-~{TX1RTS}-Pad5)") (class "Default")
      (node (ref "U4") (pin "5") (pinfunction "~{TX1RTS}_5") (pintype "passive"))
    )
    (net (code "148") (name "unconnected-(U4-~{TX2RTS}-Pad7)") (class "Default")
      (node (ref "U4") (pin "7") (pinfunction "~{TX2RTS}_7") (pintype "passive"))
    )
    (net (code "149") (name "unconnected-(U5-NC-Pad4)") (class "Default")
      (node (ref "U5") (pin "4") (pinfunction "NC_4") (pintype "passive"))
    )
    (net (code "150") (name "unconnected-(U11-Vref-Pad5)") (class "Default")
      (node (ref "U11") (pin "5") (pinfunction "Vref_5") (pintype "passive"))
    )
    (net (code "151") (name "unconnected-(U13-RTCK-Pad100)") (class "Default")
      (node (ref "U13") (pin "100") (pinfunction "RTCK_100") (pintype "passive"))
    )
    (net (code "152") (name "unconnected-(U13-TCK-Pad5)") (class "Default")
      (node (ref "U13") (pin "5") (pinfunction "TCK_5") (pintype "passive"))
    )
    (net (code "153") (name "unconnected-(U13-TDI-Pad2)") (class "Default")
      (node (ref "U13") (pin "2") (pinfunction "TDI_2") (pintype "passive"))
    )
    (net (code "154") (name "unconnected-(U13-TDO-Pad1)") (class "Default")
      (node (ref "U13") (pin "1") (pinfunction "TDO_1") (pintype "passive"))
    )
    (net (code "155") (name "unconnected-(U13-TMS-Pad3)") (class "Default")
      (node (ref "U13") (pin "3") (pinfunction "TMS_3") (pintype "passive"))
    )
    (net (code "156") (name "unconnected-(U13-~{RSTOUT}-Pad14)") (class "Default")
      (node (ref "U13") (pin "14") (pinfunction "~{RSTOUT}_14") (pintype "passive"))
    )
    (net (code "157") (name "unconnected-(U13-~{TRST}-Pad4)") (class "Default")
      (node (ref "U13") (pin "4") (pinfunction "~{TRST}_4") (pintype "passive"))
    )
    (net (code "158") (name "unconnected-(U24-~{DRDY}-Pad12)") (class "Default")
      (node (ref "U24") (pin "12") (pinfunction "~{DRDY}_12") (pintype "passive"))
    )
  )
)
